# Filter_Capacitors_-_FOTA_Digital_ICSP.net
KiCad netlist of a schematic drawn in Altium Designer
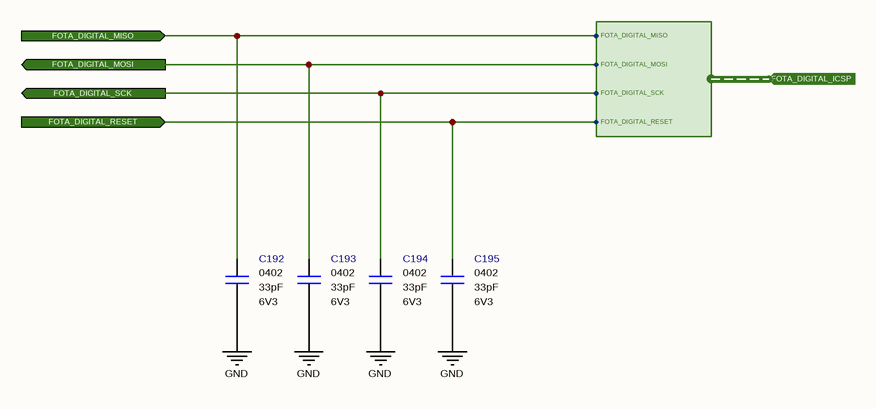
[diagram p0: Filter Capacitors - FOTA Digital ICSP.SchDoc]

(export (version "E")
  (design (tool "Eeschema 10.0.6"))
  (components
    (comp (ref "C192")
      (value "33pF")
      (footprint "CAPACITOR_0402")
      (description "Capacitor - 33pF [0402] (Ceramic)")
      (fields
        (field (name "TOLERANCE") "10%")
        (field (name "CASE") "0402")
        (field (name "VOLTAGE") "6V3")
        (field (name "MANUFACTURER PART NUMBER") "C0402C330J9RACAUTO")
      )
      (libsource (lib "Ovoo_Library") (part "Capacitor - 33pF [0402-6V3]"))
    )
    (comp (ref "C193")
      (value "33pF")
      (footprint "CAPACITOR_0402")
      (description "Capacitor - 33pF [0402] (Ceramic)")
      (fields
        (field (name "TOLERANCE") "10%")
        (field (name "CASE") "0402")
        (field (name "VOLTAGE") "6V3")
        (field (name "MANUFACTURER PART NUMBER") "C0402C330J9RACAUTO")
      )
      (libsource (lib "Ovoo_Library") (part "Capacitor - 33pF [0402-6V3]"))
    )
    (comp (ref "C194")
      (value "33pF")
      (footprint "CAPACITOR_0402")
      (description "Capacitor - 33pF [0402] (Ceramic)")
      (fields
        (field (name "TOLERANCE") "10%")
        (field (name "CASE") "0402")
        (field (name "VOLTAGE") "6V3")
        (field (name "MANUFACTURER PART NUMBER") "C0402C330J9RACAUTO")
      )
      (libsource (lib "Ovoo_Library") (part "Capacitor - 33pF [0402-6V3]"))
    )
    (comp (ref "C195")
      (value "33pF")
      (footprint "CAPACITOR_0402")
      (description "Capacitor - 33pF [0402] (Ceramic)")
      (fields
        (field (name "TOLERANCE") "10%")
        (field (name "CASE") "0402")
        (field (name "VOLTAGE") "6V3")
        (field (name "MANUFACTURER PART NUMBER") "C0402C330J9RACAUTO")
      )
      (libsource (lib "Ovoo_Library") (part "Capacitor - 33pF [0402-6V3]"))
    )
  )
  (nets
    (net (code "2") (name "/FOTA_DIGITAL_MISO") (class "Default")
      (node (ref "C192") (pin "2") (pinfunction "2_2") (pintype "passive"))
    )
    (net (code "3") (name "/FOTA_DIGITAL_MOSI") (class "Default")
      (node (ref "C193") (pin "2") (pinfunction "2_2") (pintype "passive"))
    )
    (net (code "4") (name "/FOTA_DIGITAL_RESET") (class "Default")
      (node (ref "C195") (pin "2") (pinfunction "2_2") (pintype "passive"))
    )
    (net (code "5") (name "/FOTA_DIGITAL_SCK") (class "Default")
      (node (ref "C194") (pin "2") (pinfunction "2_2") (pintype "passive"))
    )
    (net (code "7") (name "GND") (class "Default")
      (node (ref "C192") (pin "1") (pinfunction "1_1") (pintype "passive"))
      (node (ref "C193") (pin "1") (pinfunction "1_1") (pintype "passive"))
      (node (ref "C194") (pin "1") (pinfunction "1_1") (pintype "passive"))
      (node (ref "C195") (pin "1") (pinfunction "1_1") (pintype "passive"))
    )
  )
)
